# Connect_PCB.net
KiCad netlist of a schematic drawn in Altium Designer
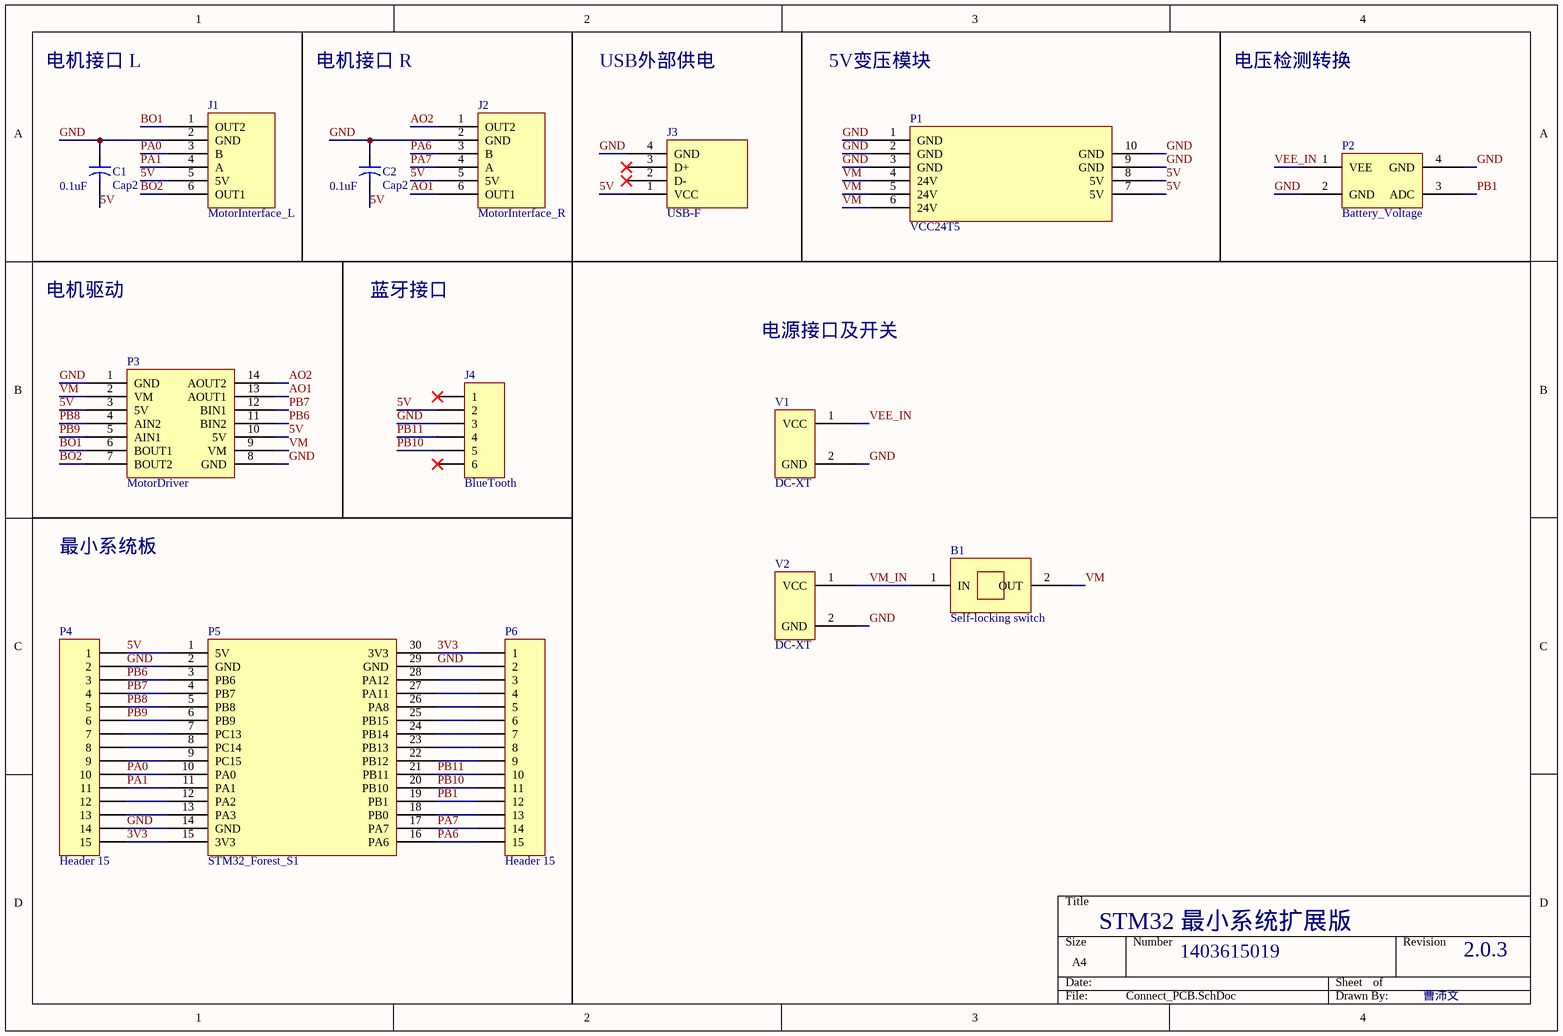
[diagram p0: Connect_PCB.SchDoc]

(export (version "E")
  (design (tool "Eeschema 10.0.6"))
  (components
    (comp (ref "B1")
      (value "Self-locking switch")
      (footprint "Self-locking switch")
      (libsource (lib "Self_Locking_Switch") (part "Self-locking switch"))
    )
    (comp (ref "C1")
      (value "Cap2")
      (footprint "CAPR5-4X5")
      (description "Capacitor")
      (fields (field (name "ALTIUM_VALUE") "0.1uF") (field (name "PUBLISHER") "Altium Limited"))
      (libsource (lib "Miscellaneous Devices") (part "Cap2"))
    )
    (comp (ref "C2")
      (value "Cap2")
      (footprint "CAPR5-4X5")
      (description "Capacitor")
      (fields (field (name "ALTIUM_VALUE") "0.1uF") (field (name "PUBLISHER") "Altium Limited"))
      (libsource (lib "Miscellaneous Devices") (part "Cap2"))
    )
    (comp (ref "J1")
      (value "MotorInterface_L")
      (footprint "MotorInterface")
      (libsource (lib "MotorInterface") (part "MotorInterface"))
    )
    (comp (ref "J2")
      (value "MotorInterface_R")
      (footprint "MotorInterface")
      (libsource (lib "MotorInterface") (part "MotorInterface"))
    )
    (comp (ref "J3") (value "USB-F") (footprint "USB-F") (libsource (lib "USB_F") (part "USB-F")))
    (comp (ref "J4")
      (value "BlueTooth")
      (footprint "HDR1X6")
      (description "Header, 6-Pin")
      (fields (field (name "PUBLISHER") "Altium Limited"))
      (libsource (lib "Miscellaneous Connectors") (part "Header 6"))
    )
    (comp (ref "P1") (value "VCC24T5") (footprint "VCC24T5") (libsource (lib "VCC24T5") (part "VCC24T5")))
    (comp (ref "P2")
      (value "Battery_Voltage")
      (footprint "PCBComponent_1")
      (libsource (lib "Battery_Voltage") (part "Battery_Voltage"))
    )
    (comp (ref "P3")
      (value "MotorDriver")
      (footprint "Motor Driver")
      (libsource (lib "MotorDriver") (part "MotorDriver"))
    )
    (comp (ref "P4")
      (value "Header 15")
      (footprint "HDR1X15")
      (description "Header, 15-Pin")
      (fields (field (name "PUBLISHER") "Altium Limited"))
      (libsource (lib "") (part "Header 15_1"))
    )
    (comp (ref "P5")
      (value "STM32_Forest_S1")
      (footprint "STM32_Forest_S1")
      (libsource (lib "STM32_Forest_S1") (part "STM32_Forest_S1"))
    )
    (comp (ref "P6")
      (value "Header 15")
      (footprint "HDR1X15")
      (description "Header, 15-Pin")
      (fields (field (name "PUBLISHER") "Altium Limited"))
      (libsource (lib "Miscellaneous Connectors") (part "Header 15"))
    )
    (comp (ref "V1") (value "DC-XT") (footprint "DC_XT") (libsource (lib "DC_XT") (part "DC-XT")))
    (comp (ref "V2") (value "DC-XT") (footprint "DC_XT") (libsource (lib "DC_XT") (part "DC-XT")))
  )
  (nets
    (net (code "1") (name "/3V3") (class "Default")
      (node (ref "P4") (pin "15") (pinfunction "15_15") (pintype "passive"))
      (node (ref "P5") (pin "15") (pinfunction "3V3_15") (pintype "passive"))
      (node (ref "P5") (pin "30") (pinfunction "3V3_30") (pintype "passive"))
      (node (ref "P6") (pin "1") (pinfunction "1_1") (pintype "passive"))
    )
    (net (code "2") (name "/5V") (class "Default")
      (node (ref "C1") (pin "2") (pinfunction "2_2") (pintype "passive"))
      (node (ref "C2") (pin "2") (pinfunction "2_2") (pintype "passive"))
      (node (ref "J1") (pin "5") (pinfunction "5V_5") (pintype "passive"))
      (node (ref "J2") (pin "5") (pinfunction "5V_5") (pintype "passive"))
      (node (ref "J3") (pin "1") (pinfunction "VCC_1") (pintype "passive"))
      (node (ref "J4") (pin "2") (pinfunction "2_2") (pintype "passive"))
      (node (ref "P1") (pin "7") (pinfunction "5V_7") (pintype "passive"))
      (node (ref "P1") (pin "8") (pinfunction "5V_8") (pintype "passive"))
      (node (ref "P3") (pin "10") (pinfunction "5V_10") (pintype "passive"))
      (node (ref "P3") (pin "3") (pinfunction "5V_3") (pintype "passive"))
      (node (ref "P4") (pin "1") (pinfunction "1_1") (pintype "passive"))
      (node (ref "P5") (pin "1") (pinfunction "5V_1") (pintype "passive"))
    )
    (net (code "3") (name "/AO1") (class "Default")
      (node (ref "J2") (pin "6") (pinfunction "OUT1_6") (pintype "passive"))
      (node (ref "P3") (pin "13") (pinfunction "AOUT1_13") (pintype "passive"))
    )
    (net (code "4") (name "/AO2") (class "Default")
      (node (ref "J2") (pin "1") (pinfunction "OUT2_1") (pintype "passive"))
      (node (ref "P3") (pin "14") (pinfunction "AOUT2_14") (pintype "passive"))
    )
    (net (code "5") (name "/BO1") (class "Default")
      (node (ref "J1") (pin "1") (pinfunction "OUT2_1") (pintype "passive"))
      (node (ref "P3") (pin "6") (pinfunction "BOUT1_6") (pintype "passive"))
    )
    (net (code "6") (name "/BO2") (class "Default")
      (node (ref "J1") (pin "6") (pinfunction "OUT1_6") (pintype "passive"))
      (node (ref "P3") (pin "7") (pinfunction "BOUT2_7") (pintype "passive"))
    )
    (net (code "7") (name "/GND") (class "Default")
      (node (ref "C1") (pin "1") (pinfunction "1_1") (pintype "passive"))
      (node (ref "C2") (pin "1") (pinfunction "1_1") (pintype "passive"))
      (node (ref "J1") (pin "2") (pinfunction "GND_2") (pintype "passive"))
      (node (ref "J2") (pin "2") (pinfunction "GND_2") (pintype "passive"))
      (node (ref "J3") (pin "4") (pinfunction "GND_4") (pintype "passive"))
      (node (ref "J4") (pin "3") (pinfunction "3_3") (pintype "passive"))
      (node (ref "P1") (pin "1") (pinfunction "GND_1") (pintype "passive"))
      (node (ref "P1") (pin "10") (pinfunction "GND_10") (pintype "passive"))
      (node (ref "P1") (pin "2") (pinfunction "GND_2") (pintype "passive"))
      (node (ref "P1") (pin "3") (pinfunction "GND_3") (pintype "passive"))
      (node (ref "P1") (pin "9") (pinfunction "GND_9") (pintype "passive"))
      (node (ref "P2") (pin "2") (pinfunction "GND_2") (pintype "passive"))
      (node (ref "P2") (pin "4") (pinfunction "GND_4") (pintype "passive"))
      (node (ref "P3") (pin "1") (pinfunction "GND_1") (pintype "passive"))
      (node (ref "P3") (pin "8") (pinfunction "GND_8") (pintype "passive"))
      (node (ref "P4") (pin "14") (pinfunction "14_14") (pintype "passive"))
      (node (ref "P4") (pin "2") (pinfunction "2_2") (pintype "passive"))
      (node (ref "P5") (pin "14") (pinfunction "GND_14") (pintype "passive"))
      (node (ref "P5") (pin "2") (pinfunction "GND_2") (pintype "passive"))
      (node (ref "P5") (pin "29") (pinfunction "GND_29") (pintype "passive"))
      (node (ref "P6") (pin "2") (pinfunction "2_2") (pintype "passive"))
      (node (ref "V1") (pin "2") (pinfunction "GND_2") (pintype "passive"))
      (node (ref "V2") (pin "2") (pinfunction "GND_2") (pintype "passive"))
    )
    (net (code "8") (name "/PA0") (class "Default")
      (node (ref "J1") (pin "3") (pinfunction "B_3") (pintype "passive"))
      (node (ref "P4") (pin "10") (pinfunction "10_10") (pintype "passive"))
      (node (ref "P5") (pin "10") (pinfunction "PA0_10") (pintype "passive"))
    )
    (net (code "9") (name "/PA1") (class "Default")
      (node (ref "J1") (pin "4") (pinfunction "A_4") (pintype "passive"))
      (node (ref "P4") (pin "11") (pinfunction "11_11") (pintype "passive"))
      (node (ref "P5") (pin "11") (pinfunction "PA1_11") (pintype "passive"))
    )
    (net (code "10") (name "/PA6") (class "Default")
      (node (ref "J2") (pin "3") (pinfunction "B_3") (pintype "passive"))
      (node (ref "P5") (pin "16") (pinfunction "PA6_16") (pintype "passive"))
      (node (ref "P6") (pin "15") (pinfunction "15_15") (pintype "passive"))
    )
    (net (code "11") (name "/PA7") (class "Default")
      (node (ref "J2") (pin "4") (pinfunction "A_4") (pintype "passive"))
      (node (ref "P5") (pin "17") (pinfunction "PA7_17") (pintype "passive"))
      (node (ref "P6") (pin "14") (pinfunction "14_14") (pintype "passive"))
    )
    (net (code "12") (name "/PB1") (class "Default")
      (node (ref "P2") (pin "3") (pinfunction "ADC_3") (pintype "passive"))
      (node (ref "P5") (pin "19") (pinfunction "PB1_19") (pintype "passive"))
      (node (ref "P6") (pin "12") (pinfunction "12_12") (pintype "passive"))
    )
    (net (code "13") (name "/PB6") (class "Default")
      (node (ref "P3") (pin "11") (pinfunction "BIN2_11") (pintype "passive"))
      (node (ref "P4") (pin "3") (pinfunction "3_3") (pintype "passive"))
      (node (ref "P5") (pin "3") (pinfunction "PB6_3") (pintype "passive"))
    )
    (net (code "14") (name "/PB7") (class "Default")
      (node (ref "P3") (pin "12") (pinfunction "BIN1_12") (pintype "passive"))
      (node (ref "P4") (pin "4") (pinfunction "4_4") (pintype "passive"))
      (node (ref "P5") (pin "4") (pinfunction "PB7_4") (pintype "passive"))
    )
    (net (code "15") (name "/PB8") (class "Default")
      (node (ref "P3") (pin "4") (pinfunction "AIN2_4") (pintype "passive"))
      (node (ref "P4") (pin "5") (pinfunction "5_5") (pintype "passive"))
      (node (ref "P5") (pin "5") (pinfunction "PB8_5") (pintype "passive"))
    )
    (net (code "16") (name "/PB9") (class "Default")
      (node (ref "P3") (pin "5") (pinfunction "AIN1_5") (pintype "passive"))
      (node (ref "P4") (pin "6") (pinfunction "6_6") (pintype "passive"))
      (node (ref "P5") (pin "6") (pinfunction "PB9_6") (pintype "passive"))
    )
    (net (code "17") (name "/PB10") (class "Default")
      (node (ref "J4") (pin "5") (pinfunction "5_5") (pintype "passive"))
      (node (ref "P5") (pin "20") (pinfunction "PB10_20") (pintype "passive"))
      (node (ref "P6") (pin "11") (pinfunction "11_11") (pintype "passive"))
    )
    (net (code "18") (name "/PB11") (class "Default")
      (node (ref "J4") (pin "4") (pinfunction "4_4") (pintype "passive"))
      (node (ref "P5") (pin "21") (pinfunction "PB11_21") (pintype "passive"))
      (node (ref "P6") (pin "10") (pinfunction "10_10") (pintype "passive"))
    )
    (net (code "19") (name "/VEE_IN") (class "Default")
      (node (ref "P2") (pin "1") (pinfunction "VEE_1") (pintype "passive"))
      (node (ref "V1") (pin "1") (pinfunction "VCC_1") (pintype "passive"))
    )
    (net (code "20") (name "/VM") (class "Default")
      (node (ref "B1") (pin "2") (pinfunction "OUT_2") (pintype "passive"))
      (node (ref "P1") (pin "4") (pinfunction "24V_4") (pintype "passive"))
      (node (ref "P1") (pin "5") (pinfunction "24V_5") (pintype "passive"))
      (node (ref "P1") (pin "6") (pinfunction "24V_6") (pintype "passive"))
      (node (ref "P3") (pin "2") (pinfunction "VM_2") (pintype "passive"))
      (node (ref "P3") (pin "9") (pinfunction "VM_9") (pintype "passive"))
    )
    (net (code "21") (name "/VM_IN") (class "Default")
      (node (ref "B1") (pin "1") (pinfunction "IN_1") (pintype "passive"))
      (node (ref "V2") (pin "1") (pinfunction "VCC_1") (pintype "passive"))
    )
    (net (code "22") (name "Net-(P5-PA2)") (class "Default")
      (node (ref "P4") (pin "12") (pinfunction "12_12") (pintype "passive"))
      (node (ref "P5") (pin "12") (pinfunction "PA2_12") (pintype "passive"))
    )
    (net (code "23") (name "Net-(P5-PA3)") (class "Default")
      (node (ref "P4") (pin "13") (pinfunction "13_13") (pintype "passive"))
      (node (ref "P5") (pin "13") (pinfunction "PA3_13") (pintype "passive"))
    )
    (net (code "24") (name "Net-(P5-PA8)") (class "Default")
      (node (ref "P5") (pin "26") (pinfunction "PA8_26") (pintype "passive"))
      (node (ref "P6") (pin "5") (pinfunction "5_5") (pintype "passive"))
    )
    (net (code "25") (name "Net-(P5-PA11)") (class "Default")
      (node (ref "P5") (pin "27") (pinfunction "PA11_27") (pintype "passive"))
      (node (ref "P6") (pin "4") (pinfunction "4_4") (pintype "passive"))
    )
    (net (code "26") (name "Net-(P5-PA12)") (class "Default")
      (node (ref "P5") (pin "28") (pinfunction "PA12_28") (pintype "passive"))
      (node (ref "P6") (pin "3") (pinfunction "3_3") (pintype "passive"))
    )
    (net (code "27") (name "Net-(P5-PB0)") (class "Default")
      (node (ref "P5") (pin "18") (pinfunction "PB0_18") (pintype "passive"))
      (node (ref "P6") (pin "13") (pinfunction "13_13") (pintype "passive"))
    )
    (net (code "28") (name "Net-(P5-PB12)") (class "Default")
      (node (ref "P5") (pin "22") (pinfunction "PB12_22") (pintype "passive"))
      (node (ref "P6") (pin "9") (pinfunction "9_9") (pintype "passive"))
    )
    (net (code "29") (name "Net-(P5-PB13)") (class "Default")
      (node (ref "P5") (pin "23") (pinfunction "PB13_23") (pintype "passive"))
      (node (ref "P6") (pin "8") (pinfunction "8_8") (pintype "passive"))
    )
    (net (code "30") (name "Net-(P5-PB14)") (class "Default")
      (node (ref "P5") (pin "24") (pinfunction "PB14_24") (pintype "passive"))
      (node (ref "P6") (pin "7") (pinfunction "7_7") (pintype "passive"))
    )
    (net (code "31") (name "Net-(P5-PB15)") (class "Default")
      (node (ref "P5") (pin "25") (pinfunction "PB15_25") (pintype "passive"))
      (node (ref "P6") (pin "6") (pinfunction "6_6") (pintype "passive"))
    )
    (net (code "32") (name "Net-(P5-PC13)") (class "Default")
      (node (ref "P4") (pin "7") (pinfunction "7_7") (pintype "passive"))
      (node (ref "P5") (pin "7") (pinfunction "PC13_7") (pintype "passive"))
    )
    (net (code "33") (name "Net-(P5-PC14)") (class "Default")
      (node (ref "P4") (pin "8") (pinfunction "8_8") (pintype "passive"))
      (node (ref "P5") (pin "8") (pinfunction "PC14_8") (pintype "passive"))
    )
    (net (code "34") (name "Net-(P5-PC15)") (class "Default")
      (node (ref "P4") (pin "9") (pinfunction "9_9") (pintype "passive"))
      (node (ref "P5") (pin "9") (pinfunction "PC15_9") (pintype "passive"))
    )
    (net (code "35") (name "unconnected-(J3-D+-Pad3)") (class "Default")
      (node (ref "J3") (pin "3") (pinfunction "D+_3") (pintype "passive+no_connect"))
    )
    (net (code "36") (name "unconnected-(J3-D--Pad2)") (class "Default")
      (node (ref "J3") (pin "2") (pinfunction "D-_2") (pintype "passive+no_connect"))
    )
    (net (code "37") (name "unconnected-(J4-Pad1)") (class "Default")
      (node (ref "J4") (pin "1") (pinfunction "1_1") (pintype "passive+no_connect"))
    )
    (net (code "38") (name "unconnected-(J4-Pad6)") (class "Default")
      (node (ref "J4") (pin "6") (pinfunction "6_6") (pintype "passive+no_connect"))
    )
  )
)
